# transmitter_lify.net
KiCad netlist of a schematic drawn in EAGLE
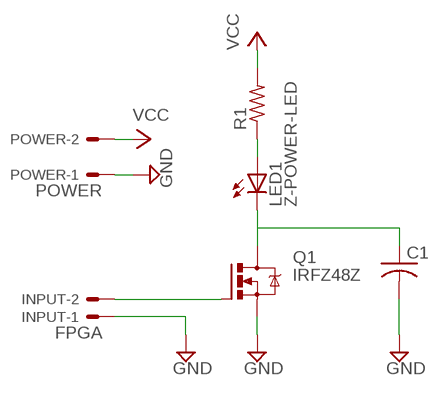
[diagram p0: schematic, sheet 1]

(export (version "E")
  (design (tool "Eeschema 10.0.6"))
  (components
    (comp (ref "C1")
      (value "C-US050-030X075")
      (footprint "eagle-import:C050-030X075")
      (libsource (lib "eagle-import") (part "C-US050-030X075"))
    )
    (comp (ref "INPUT")
      (value "FPGA")
      (footprint "eagle-import:22-23-2021")
      (fields (field (name "MF") "MOLEX") (field (name "MPN") "22-23-2021"))
      (libsource (lib "eagle-import") (part "22-23-2021"))
    )
    (comp (ref "LED1")
      (value "Z-POWER-LED")
      (footprint "eagle-import:Z-POWER-LED-PCB-TYPE")
      (libsource (lib "eagle-import") (part "Z-POWER-LED"))
    )
    (comp (ref "POWER")
      (value "POWER")
      (footprint "eagle-import:22-23-2021")
      (fields (field (name "MF") "MOLEX") (field (name "MPN") "22-23-2021"))
      (libsource (lib "eagle-import") (part "22-23-2021"))
    )
    (comp (ref "Q1")
      (value "IRFZ48Z")
      (footprint "eagle-import:TO220BH")
      (libsource (lib "eagle-import") (part "IRFZ48Z"))
    )
    (comp (ref "R1")
      (value "R-US_0411/12")
      (footprint "eagle-import:0411_12")
      (libsource (lib "eagle-import") (part "R-US_0411/12"))
    )
  )
  (nets
    (net (code "1") (name "GND") (class "Default")
      (node (ref "C1") (pin "2") (pinfunction "2_2") (pintype "passive"))
      (node (ref "INPUT") (pin "1") (pinfunction "S_1") (pintype "passive"))
      (node (ref "POWER") (pin "1") (pinfunction "S_1") (pintype "passive"))
      (node (ref "Q1") (pin "S") (pinfunction "S_S") (pintype "passive"))
    )
    (net (code "2") (name "Net-(C1-Pad1)") (class "Default")
      (node (ref "C1") (pin "1") (pinfunction "1_1") (pintype "passive"))
      (node (ref "LED1") (pin "C") (pinfunction "C_C") (pintype "passive"))
      (node (ref "Q1") (pin "D") (pinfunction "D_D") (pintype "passive"))
    )
    (net (code "3") (name "Net-(INPUTB-S)") (class "Default")
      (node (ref "INPUT") (pin "2") (pinfunction "S_2") (pintype "passive"))
      (node (ref "Q1") (pin "G") (pinfunction "G_G") (pintype "passive"))
    )
    (net (code "4") (name "Net-(LED1-PadA)") (class "Default")
      (node (ref "LED1") (pin "A") (pinfunction "A_A") (pintype "passive"))
      (node (ref "R1") (pin "1") (pinfunction "1_1") (pintype "passive"))
    )
    (net (code "5") (name "VCC") (class "Default")
      (node (ref "POWER") (pin "2") (pinfunction "S_2") (pintype "passive"))
      (node (ref "R1") (pin "2") (pinfunction "2_2") (pintype "passive"))
    )
  )
)
